# lab2h.net
KiCad netlist of a schematic drawn in EAGLE
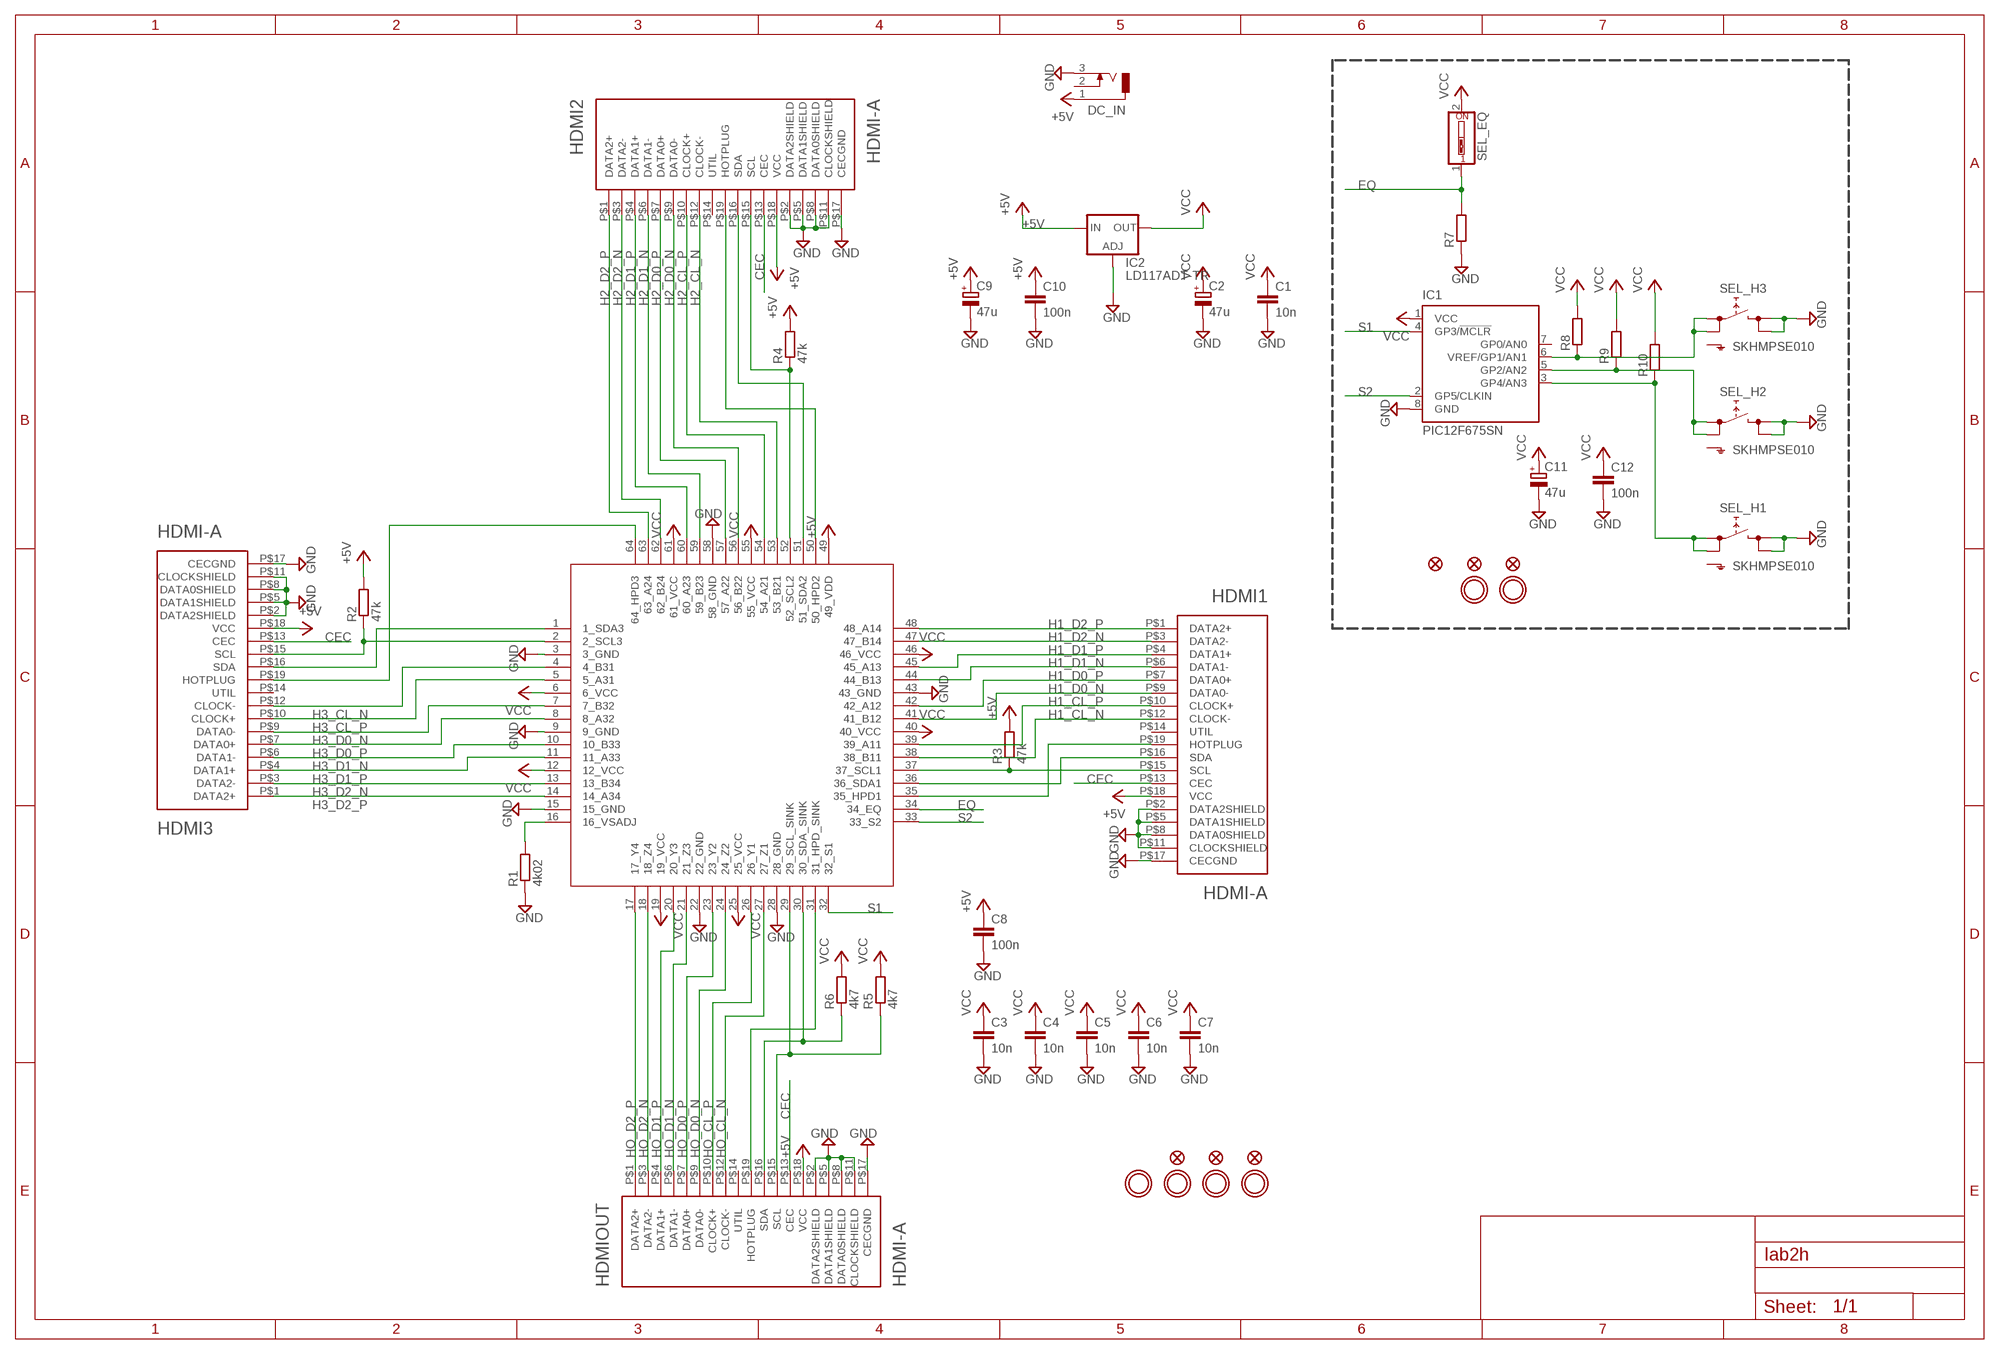
[diagram p0: schematic, sheet 1]

(export (version "E")
  (design (tool "Eeschema 10.0.6"))
  (components
    (comp (ref "C1")
      (value "10n")
      (footprint "eagle-import:C0402")
      (libsource (lib "eagle-import") (part "C-EUC0402"))
    )
    (comp (ref "C2")
      (value "47u")
      (footprint "eagle-import:SMC_A")
      (libsource (lib "eagle-import") (part "CPOL-EUSMCA"))
    )
    (comp (ref "C3")
      (value "10n")
      (footprint "eagle-import:0402")
      (libsource (lib "eagle-import") (part "C0402"))
    )
    (comp (ref "C4")
      (value "10n")
      (footprint "eagle-import:0402")
      (libsource (lib "eagle-import") (part "C0402"))
    )
    (comp (ref "C5")
      (value "10n")
      (footprint "eagle-import:0402")
      (libsource (lib "eagle-import") (part "C0402"))
    )
    (comp (ref "C6")
      (value "10n")
      (footprint "eagle-import:0402")
      (libsource (lib "eagle-import") (part "C0402"))
    )
    (comp (ref "C7")
      (value "10n")
      (footprint "eagle-import:0402")
      (libsource (lib "eagle-import") (part "C0402"))
    )
    (comp (ref "C8")
      (value "100n")
      (footprint "eagle-import:0402")
      (libsource (lib "eagle-import") (part "C0402"))
    )
    (comp (ref "C9")
      (value "47u")
      (footprint "eagle-import:SMC_A")
      (libsource (lib "eagle-import") (part "CPOL-EUSMCA"))
    )
    (comp (ref "C10")
      (value "100n")
      (footprint "eagle-import:C0402")
      (libsource (lib "eagle-import") (part "C-EUC0402"))
    )
    (comp (ref "C11")
      (value "47u")
      (footprint "eagle-import:SMC_A")
      (libsource (lib "eagle-import") (part "CPOL-EUSMCA"))
    )
    (comp (ref "C12")
      (value "100n")
      (footprint "eagle-import:C0402")
      (libsource (lib "eagle-import") (part "C-EUC0402"))
    )
    (comp (ref "DC_IN")
      (value "DCJ0303")
      (footprint "eagle-import:DCJ0303")
      (libsource (lib "eagle-import") (part "DCJ0303"))
    )
    (comp (ref "FID1")
      (value "FIDUCIAL\"\"")
      (footprint "eagle-import:FIDUCIAL_1MM")
      (libsource (lib "eagle-import") (part "FIDUCIAL{dblquote}{dblquote}"))
    )
    (comp (ref "FID2")
      (value "FIDUCIAL\"\"")
      (footprint "eagle-import:FIDUCIAL_1MM")
      (libsource (lib "eagle-import") (part "FIDUCIAL{dblquote}{dblquote}"))
    )
    (comp (ref "FID3")
      (value "FIDUCIAL\"\"")
      (footprint "eagle-import:FIDUCIAL_1MM")
      (libsource (lib "eagle-import") (part "FIDUCIAL{dblquote}{dblquote}"))
    )
    (comp (ref "FID4")
      (value "FIDUCIAL\"\"")
      (footprint "eagle-import:FIDUCIAL_1MM")
      (libsource (lib "eagle-import") (part "FIDUCIAL{dblquote}{dblquote}"))
    )
    (comp (ref "FID5")
      (value "FIDUCIAL\"\"")
      (footprint "eagle-import:FIDUCIAL_1MM")
      (libsource (lib "eagle-import") (part "FIDUCIAL{dblquote}{dblquote}"))
    )
    (comp (ref "FID6")
      (value "FIDUCIAL\"\"")
      (footprint "eagle-import:FIDUCIAL_1MM")
      (libsource (lib "eagle-import") (part "FIDUCIAL{dblquote}{dblquote}"))
    )
    (comp (ref "HDMI1")
      (value "HDMI-A")
      (footprint "eagle-import:HDMI_A")
      (libsource (lib "eagle-import") (part "HDMI-A"))
    )
    (comp (ref "HDMI2")
      (value "HDMI-A")
      (footprint "eagle-import:HDMI_A")
      (libsource (lib "eagle-import") (part "HDMI-A"))
    )
    (comp (ref "HDMI3")
      (value "HDMI-A")
      (footprint "eagle-import:HDMI_A")
      (libsource (lib "eagle-import") (part "HDMI-A"))
    )
    (comp (ref "HDMIOUT")
      (value "HDMI-A")
      (footprint "eagle-import:HDMI_A")
      (libsource (lib "eagle-import") (part "HDMI-A"))
    )
    (comp (ref "IC1")
      (value "PIC12F675SN")
      (footprint "eagle-import:SO-08")
      (fields (field (name "MF") "MICROCHIP") (field (name "MPN") "PIC12F675-E/SN"))
      (libsource (lib "eagle-import") (part "PIC12F675SN"))
    )
    (comp (ref "IC2")
      (value "LD117ADT-TR")
      (footprint "eagle-import:DPACK")
      (libsource (lib "eagle-import") (part "LD117A?DT-TR"))
    )
    (comp (ref "R1")
      (value "4k02")
      (footprint "eagle-import:0402")
      (libsource (lib "eagle-import") (part "R0402"))
    )
    (comp (ref "R2")
      (value "47k")
      (footprint "eagle-import:0402")
      (libsource (lib "eagle-import") (part "R0402"))
    )
    (comp (ref "R3")
      (value "47k")
      (footprint "eagle-import:0402")
      (libsource (lib "eagle-import") (part "R0402"))
    )
    (comp (ref "R4")
      (value "47k")
      (footprint "eagle-import:0402")
      (libsource (lib "eagle-import") (part "R0402"))
    )
    (comp (ref "R5")
      (value "4k7")
      (footprint "eagle-import:0402")
      (libsource (lib "eagle-import") (part "R0402"))
    )
    (comp (ref "R6")
      (value "4k7")
      (footprint "eagle-import:0402")
      (libsource (lib "eagle-import") (part "R0402"))
    )
    (comp (ref "R7")
      (value "R-EU_R0805")
      (footprint "eagle-import:R0805")
      (libsource (lib "eagle-import") (part "R-EU_R0805"))
    )
    (comp (ref "R8")
      (value "R-EU_R0805")
      (footprint "eagle-import:R0805")
      (libsource (lib "eagle-import") (part "R-EU_R0805"))
    )
    (comp (ref "R9")
      (value "R-EU_R0805")
      (footprint "eagle-import:R0805")
      (libsource (lib "eagle-import") (part "R-EU_R0805"))
    )
    (comp (ref "R10")
      (value "R-EU_R0805")
      (footprint "eagle-import:R0805")
      (libsource (lib "eagle-import") (part "R-EU_R0805"))
    )
    (comp (ref "SEL_EQ")
      (value "SW_DIP-1")
      (footprint "eagle-import:EDG-01")
      (libsource (lib "eagle-import") (part "SW_DIP-1"))
    )
    (comp (ref "SEL_H1")
      (value "SKHMPSE010")
      (footprint "eagle-import:SKHMPXE010")
      (libsource (lib "eagle-import") (part "SKHMPE010S"))
    )
    (comp (ref "SEL_H2")
      (value "SKHMPSE010")
      (footprint "eagle-import:SKHMPXE010")
      (libsource (lib "eagle-import") (part "SKHMPE010S"))
    )
    (comp (ref "SEL_H3")
      (value "SKHMPSE010")
      (footprint "eagle-import:SKHMPXE010")
      (libsource (lib "eagle-import") (part "SKHMPE010S"))
    )
    (comp (ref "U$1")
      (value "MOUNTINGHOLE3.0")
      (footprint "eagle-import:MOUNTINGHOLE_3.0_PLATED")
      (libsource (lib "eagle-import") (part "MOUNTINGHOLE3.0"))
    )
    (comp (ref "U$2")
      (value "MOUNTINGHOLE3.0")
      (footprint "eagle-import:MOUNTINGHOLE_3.0_PLATED")
      (libsource (lib "eagle-import") (part "MOUNTINGHOLE3.0"))
    )
    (comp (ref "U$31")
      (value "MOUNTINGHOLE3.0")
      (footprint "eagle-import:MOUNTINGHOLE_3.0_PLATED")
      (libsource (lib "eagle-import") (part "MOUNTINGHOLE3.0"))
    )
    (comp (ref "U$32")
      (value "MOUNTINGHOLE3.0")
      (footprint "eagle-import:MOUNTINGHOLE_3.0_PLATED")
      (libsource (lib "eagle-import") (part "MOUNTINGHOLE3.0"))
    )
    (comp (ref "U$33")
      (value "MOUNTINGHOLE3.0")
      (footprint "eagle-import:MOUNTINGHOLE_3.0_PLATED")
      (libsource (lib "eagle-import") (part "MOUNTINGHOLE3.0"))
    )
    (comp (ref "U$34")
      (value "MOUNTINGHOLE3.0")
      (footprint "eagle-import:MOUNTINGHOLE_3.0_PLATED")
      (libsource (lib "eagle-import") (part "MOUNTINGHOLE3.0"))
    )
    (comp (ref "U1")
      (value "TMDS351TQFP64")
      (footprint "eagle-import:QFP50P1200X1200X120-64")
      (libsource (lib "eagle-import") (part "TMDS351TQFP64"))
    )
  )
  (nets
    (net (code "1") (name "+5V") (class "Default")
      (node (ref "C10") (pin "1") (pinfunction "1_1") (pintype "passive"))
      (node (ref "C8") (pin "1") (pinfunction "1_1") (pintype "passive"))
      (node (ref "C9") (pin "+") (pinfunction "+_+") (pintype "passive"))
      (node (ref "DC_IN") (pin "1") (pinfunction "1_1") (pintype "passive"))
      (node (ref "HDMI1") (pin "P$18") (pinfunction "VCC_P$18") (pintype "bidirectional"))
      (node (ref "HDMI2") (pin "P$18") (pinfunction "VCC_P$18") (pintype "bidirectional"))
      (node (ref "HDMI3") (pin "P$18") (pinfunction "VCC_P$18") (pintype "bidirectional"))
      (node (ref "HDMIOUT") (pin "P$18") (pinfunction "VCC_P$18") (pintype "bidirectional"))
      (node (ref "IC2") (pin "3") (pinfunction "IN_3") (pintype "input"))
      (node (ref "R2") (pin "2") (pinfunction "2_2") (pintype "passive"))
      (node (ref "R3") (pin "2") (pinfunction "2_2") (pintype "passive"))
      (node (ref "R4") (pin "2") (pinfunction "2_2") (pintype "passive"))
      (node (ref "U1") (pin "49") (pinfunction "49_VDD_49") (pintype "bidirectional"))
    )
    (net (code "2") (name "/CEC") (class "Default")
      (node (ref "HDMI1") (pin "P$13") (pinfunction "CEC_P$13") (pintype "bidirectional"))
      (node (ref "HDMI2") (pin "P$13") (pinfunction "CEC_P$13") (pintype "bidirectional"))
      (node (ref "HDMI3") (pin "P$13") (pinfunction "CEC_P$13") (pintype "bidirectional"))
      (node (ref "HDMIOUT") (pin "P$13") (pinfunction "CEC_P$13") (pintype "bidirectional"))
    )
    (net (code "3") (name "/EQ") (class "Default")
      (node (ref "R7") (pin "2") (pinfunction "2_2") (pintype "passive"))
      (node (ref "SEL_EQ") (pin "1") (pinfunction "1_1") (pintype "passive"))
      (node (ref "U1") (pin "34") (pinfunction "34_EQ_34") (pintype "bidirectional"))
    )
    (net (code "4") (name "/H1_CL_N") (class "Default")
      (node (ref "HDMI1") (pin "P$12") (pinfunction "CLOCK-_P$12") (pintype "bidirectional"))
      (node (ref "U1") (pin "38") (pinfunction "38_B11_38") (pintype "bidirectional"))
    )
    (net (code "5") (name "/H1_CL_P") (class "Default")
      (node (ref "HDMI1") (pin "P$10") (pinfunction "CLOCK+_P$10") (pintype "bidirectional"))
      (node (ref "U1") (pin "39") (pinfunction "39_A11_39") (pintype "bidirectional"))
    )
    (net (code "6") (name "/H1_D0_N") (class "Default")
      (node (ref "HDMI1") (pin "P$9") (pinfunction "DATA0-_P$9") (pintype "bidirectional"))
      (node (ref "U1") (pin "41") (pinfunction "41_B12_41") (pintype "bidirectional"))
    )
    (net (code "7") (name "/H1_D0_P") (class "Default")
      (node (ref "HDMI1") (pin "P$7") (pinfunction "DATA0+_P$7") (pintype "bidirectional"))
      (node (ref "U1") (pin "42") (pinfunction "42_A12_42") (pintype "bidirectional"))
    )
    (net (code "8") (name "/H1_D1_N") (class "Default")
      (node (ref "HDMI1") (pin "P$6") (pinfunction "DATA1-_P$6") (pintype "bidirectional"))
      (node (ref "U1") (pin "44") (pinfunction "44_B13_44") (pintype "bidirectional"))
    )
    (net (code "9") (name "/H1_D1_P") (class "Default")
      (node (ref "HDMI1") (pin "P$4") (pinfunction "DATA1+_P$4") (pintype "bidirectional"))
      (node (ref "U1") (pin "45") (pinfunction "45_A13_45") (pintype "bidirectional"))
    )
    (net (code "10") (name "/H1_D2_N") (class "Default")
      (node (ref "HDMI1") (pin "P$3") (pinfunction "DATA2-_P$3") (pintype "bidirectional"))
      (node (ref "U1") (pin "47") (pinfunction "47_B14_47") (pintype "bidirectional"))
    )
    (net (code "11") (name "/H1_D2_P") (class "Default")
      (node (ref "HDMI1") (pin "P$1") (pinfunction "DATA2+_P$1") (pintype "bidirectional"))
      (node (ref "U1") (pin "48") (pinfunction "48_A14_48") (pintype "bidirectional"))
    )
    (net (code "12") (name "/H2_CL_N") (class "Default")
      (node (ref "HDMI2") (pin "P$12") (pinfunction "CLOCK-_P$12") (pintype "bidirectional"))
      (node (ref "U1") (pin "53") (pinfunction "53_B21_53") (pintype "bidirectional"))
    )
    (net (code "13") (name "/H2_CL_P") (class "Default")
      (node (ref "HDMI2") (pin "P$10") (pinfunction "CLOCK+_P$10") (pintype "bidirectional"))
      (node (ref "U1") (pin "54") (pinfunction "54_A21_54") (pintype "bidirectional"))
    )
    (net (code "14") (name "/H2_D0_N") (class "Default")
      (node (ref "HDMI2") (pin "P$9") (pinfunction "DATA0-_P$9") (pintype "bidirectional"))
      (node (ref "U1") (pin "56") (pinfunction "56_B22_56") (pintype "bidirectional"))
    )
    (net (code "15") (name "/H2_D0_P") (class "Default")
      (node (ref "HDMI2") (pin "P$7") (pinfunction "DATA0+_P$7") (pintype "bidirectional"))
      (node (ref "U1") (pin "57") (pinfunction "57_A22_57") (pintype "bidirectional"))
    )
    (net (code "16") (name "/H2_D1_N") (class "Default")
      (node (ref "HDMI2") (pin "P$6") (pinfunction "DATA1-_P$6") (pintype "bidirectional"))
      (node (ref "U1") (pin "59") (pinfunction "59_B23_59") (pintype "bidirectional"))
    )
    (net (code "17") (name "/H2_D1_P") (class "Default")
      (node (ref "HDMI2") (pin "P$4") (pinfunction "DATA1+_P$4") (pintype "bidirectional"))
      (node (ref "U1") (pin "60") (pinfunction "60_A23_60") (pintype "bidirectional"))
    )
    (net (code "18") (name "/H2_D2_N") (class "Default")
      (node (ref "HDMI2") (pin "P$3") (pinfunction "DATA2-_P$3") (pintype "bidirectional"))
      (node (ref "U1") (pin "62") (pinfunction "62_B24_62") (pintype "bidirectional"))
    )
    (net (code "19") (name "/H2_D2_P") (class "Default")
      (node (ref "HDMI2") (pin "P$1") (pinfunction "DATA2+_P$1") (pintype "bidirectional"))
      (node (ref "U1") (pin "63") (pinfunction "63_A24_63") (pintype "bidirectional"))
    )
    (net (code "20") (name "/H3_CL_N") (class "Default")
      (node (ref "HDMI3") (pin "P$12") (pinfunction "CLOCK-_P$12") (pintype "bidirectional"))
      (node (ref "U1") (pin "4") (pinfunction "4_B31_4") (pintype "bidirectional"))
    )
    (net (code "21") (name "/H3_CL_P") (class "Default")
      (node (ref "HDMI3") (pin "P$10") (pinfunction "CLOCK+_P$10") (pintype "bidirectional"))
      (node (ref "U1") (pin "5") (pinfunction "5_A31_5") (pintype "bidirectional"))
    )
    (net (code "22") (name "/H3_D0_N") (class "Default")
      (node (ref "HDMI3") (pin "P$9") (pinfunction "DATA0-_P$9") (pintype "bidirectional"))
      (node (ref "U1") (pin "7") (pinfunction "7_B32_7") (pintype "bidirectional"))
    )
    (net (code "23") (name "/H3_D0_P") (class "Default")
      (node (ref "HDMI3") (pin "P$7") (pinfunction "DATA0+_P$7") (pintype "bidirectional"))
      (node (ref "U1") (pin "8") (pinfunction "8_A32_8") (pintype "bidirectional"))
    )
    (net (code "24") (name "/H3_D1_N") (class "Default")
      (node (ref "HDMI3") (pin "P$6") (pinfunction "DATA1-_P$6") (pintype "bidirectional"))
      (node (ref "U1") (pin "10") (pinfunction "10_B33_10") (pintype "bidirectional"))
    )
    (net (code "25") (name "/H3_D1_P") (class "Default")
      (node (ref "HDMI3") (pin "P$4") (pinfunction "DATA1+_P$4") (pintype "bidirectional"))
      (node (ref "U1") (pin "11") (pinfunction "11_A33_11") (pintype "bidirectional"))
    )
    (net (code "26") (name "/H3_D2_N") (class "Default")
      (node (ref "HDMI3") (pin "P$3") (pinfunction "DATA2-_P$3") (pintype "bidirectional"))
      (node (ref "U1") (pin "13") (pinfunction "13_B34_13") (pintype "bidirectional"))
    )
    (net (code "27") (name "/H3_D2_P") (class "Default")
      (node (ref "HDMI3") (pin "P$1") (pinfunction "DATA2+_P$1") (pintype "bidirectional"))
      (node (ref "U1") (pin "14") (pinfunction "14_A34_14") (pintype "bidirectional"))
    )
    (net (code "28") (name "/HO_CL_N") (class "Default")
      (node (ref "HDMIOUT") (pin "P$12") (pinfunction "CLOCK-_P$12") (pintype "bidirectional"))
      (node (ref "U1") (pin "27") (pinfunction "27_Z1_27") (pintype "bidirectional"))
    )
    (net (code "29") (name "/HO_CL_P") (class "Default")
      (node (ref "HDMIOUT") (pin "P$10") (pinfunction "CLOCK+_P$10") (pintype "bidirectional"))
      (node (ref "U1") (pin "26") (pinfunction "26_Y1_26") (pintype "bidirectional"))
    )
    (net (code "30") (name "/HO_D0_N") (class "Default")
      (node (ref "HDMIOUT") (pin "P$9") (pinfunction "DATA0-_P$9") (pintype "bidirectional"))
      (node (ref "U1") (pin "24") (pinfunction "24_Z2_24") (pintype "bidirectional"))
    )
    (net (code "31") (name "/HO_D0_P") (class "Default")
      (node (ref "HDMIOUT") (pin "P$7") (pinfunction "DATA0+_P$7") (pintype "bidirectional"))
      (node (ref "U1") (pin "23") (pinfunction "23_Y2_23") (pintype "bidirectional"))
    )
    (net (code "32") (name "/HO_D1_N") (class "Default")
      (node (ref "HDMIOUT") (pin "P$6") (pinfunction "DATA1-_P$6") (pintype "bidirectional"))
      (node (ref "U1") (pin "21") (pinfunction "21_Z3_21") (pintype "bidirectional"))
    )
    (net (code "33") (name "/HO_D1_P") (class "Default")
      (node (ref "HDMIOUT") (pin "P$4") (pinfunction "DATA1+_P$4") (pintype "bidirectional"))
      (node (ref "U1") (pin "20") (pinfunction "20_Y3_20") (pintype "bidirectional"))
    )
    (net (code "34") (name "/HO_D2_N") (class "Default")
      (node (ref "HDMIOUT") (pin "P$3") (pinfunction "DATA2-_P$3") (pintype "bidirectional"))
      (node (ref "U1") (pin "18") (pinfunction "18_Z4_18") (pintype "bidirectional"))
    )
    (net (code "35") (name "/HO_D2_P") (class "Default")
      (node (ref "HDMIOUT") (pin "P$1") (pinfunction "DATA2+_P$1") (pintype "bidirectional"))
      (node (ref "U1") (pin "17") (pinfunction "17_Y4_17") (pintype "bidirectional"))
    )
    (net (code "36") (name "/S1") (class "Default")
      (node (ref "IC1") (pin "4") (pinfunction "GP3/~{MCLR}_4") (pintype "input"))
      (node (ref "U1") (pin "32") (pinfunction "32_S1_32") (pintype "bidirectional"))
    )
    (net (code "37") (name "/S2") (class "Default")
      (node (ref "IC1") (pin "2") (pinfunction "GP5/CLKIN_2") (pintype "bidirectional"))
      (node (ref "U1") (pin "33") (pinfunction "33_S2_33") (pintype "bidirectional"))
    )
    (net (code "38") (name "GND") (class "Default")
      (node (ref "C1") (pin "2") (pinfunction "2_2") (pintype "passive"))
      (node (ref "C10") (pin "2") (pinfunction "2_2") (pintype "passive"))
      (node (ref "C11") (pin "-") (pinfunction "-_-") (pintype "passive"))
      (node (ref "C12") (pin "2") (pinfunction "2_2") (pintype "passive"))
      (node (ref "C2") (pin "-") (pinfunction "-_-") (pintype "passive"))
      (node (ref "C3") (pin "2") (pinfunction "2_2") (pintype "passive"))
      (node (ref "C4") (pin "2") (pinfunction "2_2") (pintype "passive"))
      (node (ref "C5") (pin "2") (pinfunction "2_2") (pintype "passive"))
      (node (ref "C6") (pin "2") (pinfunction "2_2") (pintype "passive"))
      (node (ref "C7") (pin "2") (pinfunction "2_2") (pintype "passive"))
      (node (ref "C8") (pin "2") (pinfunction "2_2") (pintype "passive"))
      (node (ref "C9") (pin "-") (pinfunction "-_-") (pintype "passive"))
      (node (ref "DC_IN") (pin "3") (pinfunction "3_3") (pintype "passive"))
      (node (ref "HDMI1") (pin "P$11") (pinfunction "CLOCKSHIELD_P$11") (pintype "bidirectional"))
      (node (ref "HDMI1") (pin "P$17") (pinfunction "CECGND_P$17") (pintype "bidirectional"))
      (node (ref "HDMI1") (pin "P$2") (pinfunction "DATA2SHIELD_P$2") (pintype "bidirectional"))
      (node (ref "HDMI1") (pin "P$5") (pinfunction "DATA1SHIELD_P$5") (pintype "bidirectional"))
      (node (ref "HDMI1") (pin "P$8") (pinfunction "DATA0SHIELD_P$8") (pintype "bidirectional"))
      (node (ref "HDMI2") (pin "P$11") (pinfunction "CLOCKSHIELD_P$11") (pintype "bidirectional"))
      (node (ref "HDMI2") (pin "P$17") (pinfunction "CECGND_P$17") (pintype "bidirectional"))
      (node (ref "HDMI2") (pin "P$2") (pinfunction "DATA2SHIELD_P$2") (pintype "bidirectional"))
      (node (ref "HDMI2") (pin "P$5") (pinfunction "DATA1SHIELD_P$5") (pintype "bidirectional"))
      (node (ref "HDMI2") (pin "P$8") (pinfunction "DATA0SHIELD_P$8") (pintype "bidirectional"))
      (node (ref "HDMI3") (pin "P$11") (pinfunction "CLOCKSHIELD_P$11") (pintype "bidirectional"))
      (node (ref "HDMI3") (pin "P$17") (pinfunction "CECGND_P$17") (pintype "bidirectional"))
      (node (ref "HDMI3") (pin "P$2") (pinfunction "DATA2SHIELD_P$2") (pintype "bidirectional"))
      (node (ref "HDMI3") (pin "P$5") (pinfunction "DATA1SHIELD_P$5") (pintype "bidirectional"))
      (node (ref "HDMI3") (pin "P$8") (pinfunction "DATA0SHIELD_P$8") (pintype "bidirectional"))
      (node (ref "HDMIOUT") (pin "P$11") (pinfunction "CLOCKSHIELD_P$11") (pintype "bidirectional"))
      (node (ref "HDMIOUT") (pin "P$17") (pinfunction "CECGND_P$17") (pintype "bidirectional"))
      (node (ref "HDMIOUT") (pin "P$2") (pinfunction "DATA2SHIELD_P$2") (pintype "bidirectional"))
      (node (ref "HDMIOUT") (pin "P$5") (pinfunction "DATA1SHIELD_P$5") (pintype "bidirectional"))
      (node (ref "HDMIOUT") (pin "P$8") (pinfunction "DATA0SHIELD_P$8") (pintype "bidirectional"))
      (node (ref "IC1") (pin "8") (pinfunction "GND_8") (pintype "power_in"))
      (node (ref "IC2") (pin "1") (pinfunction "ADJ_1") (pintype "input"))
      (node (ref "R1") (pin "1") (pinfunction "1_1") (pintype "passive"))
      (node (ref "R7") (pin "1") (pinfunction "1_1") (pintype "passive"))
      (node (ref "SEL_H1") (pin "3") (pinfunction "2.1_3") (pintype "passive"))
      (node (ref "SEL_H1") (pin "4") (pinfunction "2.2_4") (pintype "passive"))
      (node (ref "SEL_H2") (pin "3") (pinfunction "2.1_3") (pintype "passive"))
      (node (ref "SEL_H2") (pin "4") (pinfunction "2.2_4") (pintype "passive"))
      (node (ref "SEL_H3") (pin "3") (pinfunction "2.1_3") (pintype "passive"))
      (node (ref "SEL_H3") (pin "4") (pinfunction "2.2_4") (pintype "passive"))
      (node (ref "U1") (pin "15") (pinfunction "15_GND_15") (pintype "bidirectional"))
      (node (ref "U1") (pin "22") (pinfunction "22_GND_22") (pintype "bidirectional"))
      (node (ref "U1") (pin "28") (pinfunction "28_GND_28") (pintype "bidirectional"))
      (node (ref "U1") (pin "3") (pinfunction "3_GND_3") (pintype "bidirectional"))
      (node (ref "U1") (pin "43") (pinfunction "43_GND_43") (pintype "bidirectional"))
      (node (ref "U1") (pin "58") (pinfunction "58_GND_58") (pintype "bidirectional"))
      (node (ref "U1") (pin "9") (pinfunction "9_GND_9") (pintype "bidirectional"))
    )
    (net (code "39") (name "Net-(HDMI1-HOTPLUG)") (class "Default")
      (node (ref "HDMI1") (pin "P$19") (pinfunction "HOTPLUG_P$19") (pintype "bidirectional"))
      (node (ref "U1") (pin "35") (pinfunction "35_HPD1_35") (pintype "bidirectional"))
    )
    (net (code "40") (name "Net-(HDMI1-SCL)") (class "Default")
      (node (ref "HDMI1") (pin "P$15") (pinfunction "SCL_P$15") (pintype "bidirectional"))
      (node (ref "R3") (pin "1") (pinfunction "1_1") (pintype "passive"))
      (node (ref "U1") (pin "37") (pinfunction "37_SCL1_37") (pintype "bidirectional"))
    )
    (net (code "41") (name "Net-(HDMI1-SDA)") (class "Default")
      (node (ref "HDMI1") (pin "P$16") (pinfunction "SDA_P$16") (pintype "bidirectional"))
      (node (ref "U1") (pin "36") (pinfunction "36_SDA1_36") (pintype "bidirectional"))
    )
    (net (code "42") (name "Net-(HDMI2-HOTPLUG)") (class "Default")
      (node (ref "HDMI2") (pin "P$19") (pinfunction "HOTPLUG_P$19") (pintype "bidirectional"))
      (node (ref "U1") (pin "50") (pinfunction "50_HPD2_50") (pintype "bidirectional"))
    )
    (net (code "43") (name "Net-(HDMI2-SCL)") (class "Default")
      (node (ref "HDMI2") (pin "P$15") (pinfunction "SCL_P$15") (pintype "bidirectional"))
      (node (ref "R4") (pin "1") (pinfunction "1_1") (pintype "passive"))
      (node (ref "U1") (pin "52") (pinfunction "52_SCL2_52") (pintype "bidirectional"))
    )
    (net (code "44") (name "Net-(HDMI2-SDA)") (class "Default")
      (node (ref "HDMI2") (pin "P$16") (pinfunction "SDA_P$16") (pintype "bidirectional"))
      (node (ref "U1") (pin "51") (pinfunction "51_SDA2_51") (pintype "bidirectional"))
    )
    (net (code "45") (name "Net-(HDMI3-HOTPLUG)") (class "Default")
      (node (ref "HDMI3") (pin "P$19") (pinfunction "HOTPLUG_P$19") (pintype "bidirectional"))
      (node (ref "U1") (pin "64") (pinfunction "64_HPD3_64") (pintype "bidirectional"))
    )
    (net (code "46") (name "Net-(HDMI3-SCL)") (class "Default")
      (node (ref "HDMI3") (pin "P$15") (pinfunction "SCL_P$15") (pintype "bidirectional"))
      (node (ref "R2") (pin "1") (pinfunction "1_1") (pintype "passive"))
      (node (ref "U1") (pin "2") (pinfunction "2_SCL3_2") (pintype "bidirectional"))
    )
    (net (code "47") (name "Net-(HDMI3-SDA)") (class "Default")
      (node (ref "HDMI3") (pin "P$16") (pinfunction "SDA_P$16") (pintype "bidirectional"))
      (node (ref "U1") (pin "1") (pinfunction "1_SDA3_1") (pintype "bidirectional"))
    )
    (net (code "48") (name "Net-(HDMIOUT-HOTPLUG)") (class "Default")
      (node (ref "HDMIOUT") (pin "P$19") (pinfunction "HOTPLUG_P$19") (pintype "bidirectional"))
      (node (ref "U1") (pin "31") (pinfunction "31_HPD_SINK_31") (pintype "bidirectional"))
    )
    (net (code "49") (name "Net-(HDMIOUT-SCL)") (class "Default")
      (node (ref "HDMIOUT") (pin "P$15") (pinfunction "SCL_P$15") (pintype "bidirectional"))
      (node (ref "R5") (pin "1") (pinfunction "1_1") (pintype "passive"))
      (node (ref "U1") (pin "29") (pinfunction "29_SCL_SINK_29") (pintype "bidirectional"))
    )
    (net (code "50") (name "Net-(HDMIOUT-SDA)") (class "Default")
      (node (ref "HDMIOUT") (pin "P$16") (pinfunction "SDA_P$16") (pintype "bidirectional"))
      (node (ref "R6") (pin "1") (pinfunction "1_1") (pintype "passive"))
      (node (ref "U1") (pin "30") (pinfunction "30_SDA_SINK_30") (pintype "bidirectional"))
    )
    (net (code "51") (name "Net-(IC1-GP2{slash}AN2)") (class "Default")
      (node (ref "IC1") (pin "5") (pinfunction "GP2/AN2_5") (pintype "bidirectional"))
      (node (ref "R9") (pin "1") (pinfunction "1_1") (pintype "passive"))
      (node (ref "SEL_H2") (pin "1") (pinfunction "1.1_1") (pintype "passive"))
      (node (ref "SEL_H2") (pin "2") (pinfunction "1.2_2") (pintype "passive"))
    )
    (net (code "52") (name "Net-(IC1-GP4{slash}AN3)") (class "Default")
      (node (ref "IC1") (pin "3") (pinfunction "GP4/AN3_3") (pintype "bidirectional"))
      (node (ref "R10") (pin "1") (pinfunction "1_1") (pintype "passive"))
      (node (ref "SEL_H1") (pin "1") (pinfunction "1.1_1") (pintype "passive"))
      (node (ref "SEL_H1") (pin "2") (pinfunction "1.2_2") (pintype "passive"))
    )
    (net (code "53") (name "Net-(IC1-VREF{slash}GP1{slash}AN1)") (class "Default")
      (node (ref "IC1") (pin "6") (pinfunction "VREF/GP1/AN1_6") (pintype "bidirectional"))
      (node (ref "R8") (pin "1") (pinfunction "1_1") (pintype "passive"))
      (node (ref "SEL_H3") (pin "1") (pinfunction "1.1_1") (pintype "passive"))
      (node (ref "SEL_H3") (pin "2") (pinfunction "1.2_2") (pintype "passive"))
    )
    (net (code "54") (name "Net-(U1-16_VSADJ)") (class "Default")
      (node (ref "R1") (pin "2") (pinfunction "2_2") (pintype "passive"))
      (node (ref "U1") (pin "16") (pinfunction "16_VSADJ_16") (pintype "bidirectional"))
    )
    (net (code "55") (name "VCC") (class "Default")
      (node (ref "C1") (pin "1") (pinfunction "1_1") (pintype "passive"))
      (node (ref "C11") (pin "+") (pinfunction "+_+") (pintype "passive"))
      (node (ref "C12") (pin "1") (pinfunction "1_1") (pintype "passive"))
      (node (ref "C2") (pin "+") (pinfunction "+_+") (pintype "passive"))
      (node (ref "C3") (pin "1") (pinfunction "1_1") (pintype "passive"))
      (node (ref "C4") (pin "1") (pinfunction "1_1") (pintype "passive"))
      (node (ref "C5") (pin "1") (pinfunction "1_1") (pintype "passive"))
      (node (ref "C6") (pin "1") (pinfunction "1_1") (pintype "passive"))
      (node (ref "C7") (pin "1") (pinfunction "1_1") (pintype "passive"))
      (node (ref "IC1") (pin "1") (pinfunction "VCC_1") (pintype "power_in"))
      (node (ref "IC2") (pin "4") (pinfunction "OUT_4") (pintype "passive"))
      (node (ref "R10") (pin "2") (pinfunction "2_2") (pintype "passive"))
      (node (ref "R5") (pin "2") (pinfunction "2_2") (pintype "passive"))
      (node (ref "R6") (pin "2") (pinfunction "2_2") (pintype "passive"))
      (node (ref "R8") (pin "2") (pinfunction "2_2") (pintype "passive"))
      (node (ref "R9") (pin "2") (pinfunction "2_2") (pintype "passive"))
      (node (ref "SEL_EQ") (pin "2") (pinfunction "2_2") (pintype "passive"))
      (node (ref "U1") (pin "12") (pinfunction "12_VCC_12") (pintype "bidirectional"))
      (node (ref "U1") (pin "19") (pinfunction "19_VCC_19") (pintype "bidirectional"))
      (node (ref "U1") (pin "25") (pinfunction "25_VCC_25") (pintype "bidirectional"))
      (node (ref "U1") (pin "40") (pinfunction "40_VCC_40") (pintype "bidirectional"))
      (node (ref "U1") (pin "46") (pinfunction "46_VCC_46") (pintype "bidirectional"))
      (node (ref "U1") (pin "55") (pinfunction "55_VCC_55") (pintype "bidirectional"))
      (node (ref "U1") (pin "6") (pinfunction "6_VCC_6") (pintype "bidirectional"))
      (node (ref "U1") (pin "61") (pinfunction "61_VCC_61") (pintype "bidirectional"))
    )
    (net (code "56") (name "unconnected-(DC_IN-Pad2)") (class "Default")
      (node (ref "DC_IN") (pin "2") (pinfunction "2_2") (pintype "passive"))
    )
    (net (code "57") (name "unconnected-(HDMI1-UTIL-PadP$14)") (class "Default")
      (node (ref "HDMI1") (pin "P$14") (pinfunction "UTIL_P$14") (pintype "bidirectional"))
    )
    (net (code "58") (name "unconnected-(HDMI2-UTIL-PadP$14)") (class "Default")
      (node (ref "HDMI2") (pin "P$14") (pinfunction "UTIL_P$14") (pintype "bidirectional"))
    )
    (net (code "59") (name "unconnected-(HDMI3-UTIL-PadP$14)") (class "Default")
      (node (ref "HDMI3") (pin "P$14") (pinfunction "UTIL_P$14") (pintype "bidirectional"))
    )
    (net (code "60") (name "unconnected-(HDMIOUT-UTIL-PadP$14)") (class "Default")
      (node (ref "HDMIOUT") (pin "P$14") (pinfunction "UTIL_P$14") (pintype "bidirectional"))
    )
    (net (code "61") (name "unconnected-(IC1-GP0{slash}AN0-Pad7)") (class "Default")
      (node (ref "IC1") (pin "7") (pinfunction "GP0/AN0_7") (pintype "bidirectional"))
    )
    (net (code "62") (name "unconnected-(SEL_H1-SH-Pad5)") (class "Default")
      (node (ref "SEL_H1") (pin "5") (pinfunction "SH_5") (pintype "passive"))
    )
    (net (code "63") (name "unconnected-(SEL_H2-SH-Pad5)") (class "Default")
      (node (ref "SEL_H2") (pin "5") (pinfunction "SH_5") (pintype "passive"))
    )
    (net (code "64") (name "unconnected-(SEL_H3-SH-Pad5)") (class "Default")
      (node (ref "SEL_H3") (pin "5") (pinfunction "SH_5") (pintype "passive"))
    )
  )
)
